# STM8L-FOX_80m_PA_V5_3.net
KiCad netlist of a schematic drawn in EAGLE
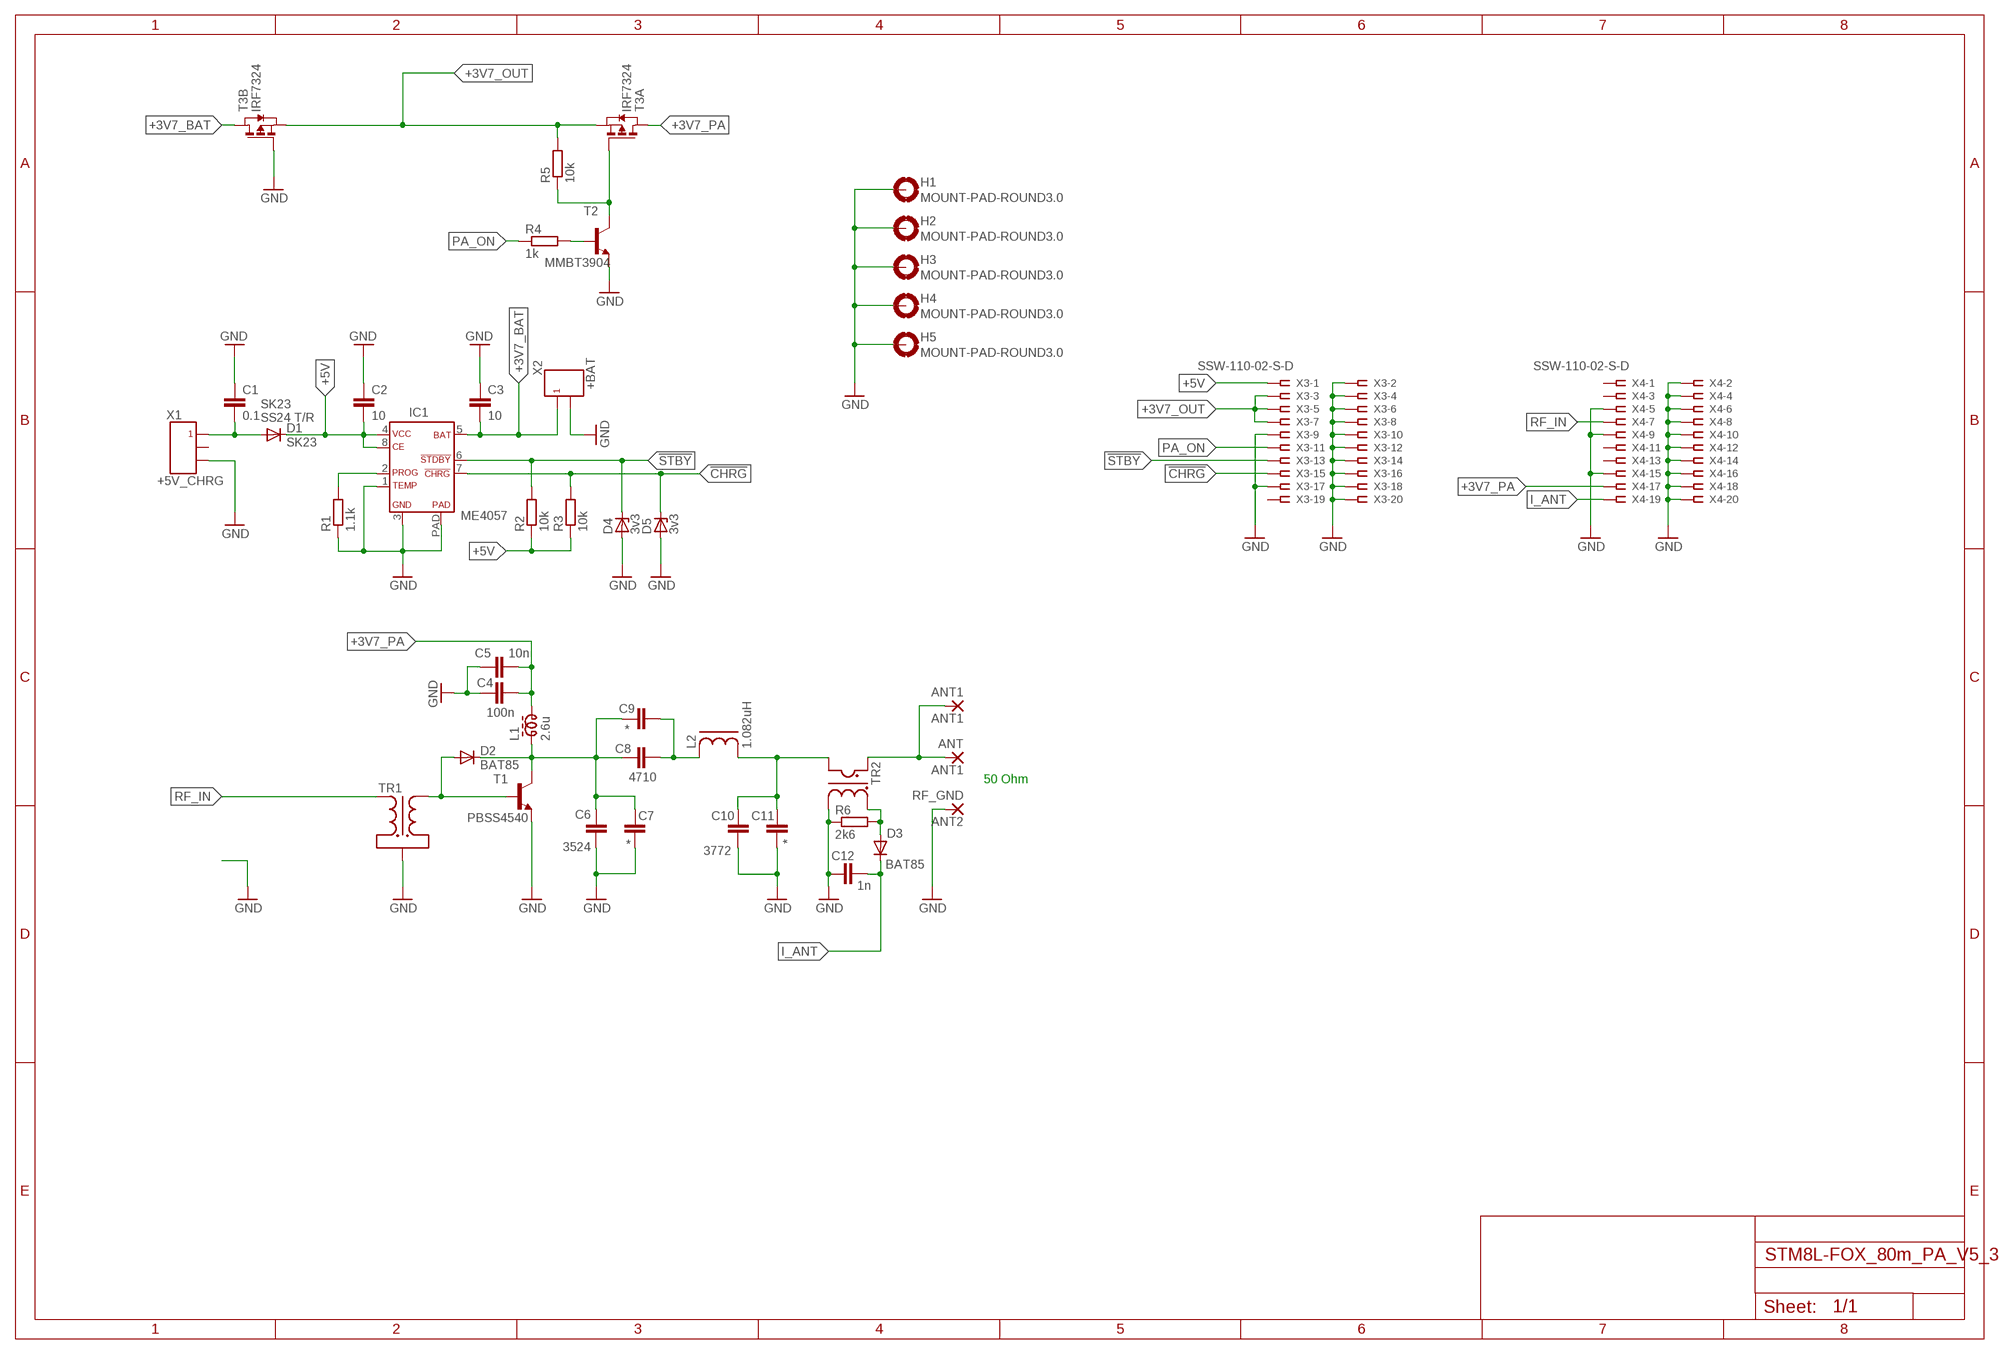
[diagram p0: schematic, sheet 1]

(export (version "E")
  (design (tool "Eeschema 10.0.6"))
  (components
    (comp (ref "ANT")
      (value "ANT1")
      (footprint "eagle-import:2,54_0,8")
      (libsource (lib "eagle-import") (part "WIREPAD2,54/0,8"))
    )
    (comp (ref "ANT1")
      (value "ANT1")
      (footprint "eagle-import:2,54_0,8")
      (libsource (lib "eagle-import") (part "WIREPAD2,54/0,8"))
    )
    (comp (ref "C1")
      (value "0.1")
      (footprint "eagle-import:C1206K")
      (libsource (lib "eagle-import") (part "C-EUC1206K"))
    )
    (comp (ref "C2")
      (value "10")
      (footprint "eagle-import:C1206K")
      (libsource (lib "eagle-import") (part "C-EUC1206K"))
    )
    (comp (ref "C3")
      (value "10")
      (footprint "eagle-import:C1206K")
      (libsource (lib "eagle-import") (part "C-EUC1206K"))
    )
    (comp (ref "C4")
      (value "100n")
      (footprint "eagle-import:C1206K")
      (libsource (lib "eagle-import") (part "C-EUC1206K"))
    )
    (comp (ref "C5")
      (value "10n")
      (footprint "eagle-import:C1206K")
      (libsource (lib "eagle-import") (part "C-EUC1206K"))
    )
    (comp (ref "C6")
      (value "3524")
      (footprint "eagle-import:C1206K")
      (libsource (lib "eagle-import") (part "C-EUC1206K"))
    )
    (comp (ref "C7")
      (value "*")
      (footprint "eagle-import:C1206K")
      (libsource (lib "eagle-import") (part "C-EUC1206K"))
    )
    (comp (ref "C8")
      (value "4710")
      (footprint "eagle-import:C1206K")
      (libsource (lib "eagle-import") (part "C-EUC1206K"))
    )
    (comp (ref "C9")
      (value "*")
      (footprint "eagle-import:C1206K")
      (libsource (lib "eagle-import") (part "C-EUC1206K"))
    )
    (comp (ref "C10")
      (value "3772")
      (footprint "eagle-import:C1206K")
      (libsource (lib "eagle-import") (part "C-EUC1206K"))
    )
    (comp (ref "C11")
      (value "*")
      (footprint "eagle-import:C1206K")
      (libsource (lib "eagle-import") (part "C-EUC1206K"))
    )
    (comp (ref "C12")
      (value "1n")
      (footprint "eagle-import:C1206K")
      (libsource (lib "eagle-import") (part "C-EUC1206K"))
    )
    (comp (ref "D1")
      (value "SK23")
      (footprint "eagle-import:DO-214AC")
      (libsource (lib "eagle-import") (part "DIODE-DO-214AC"))
    )
    (comp (ref "D2")
      (value "BAT85")
      (footprint "eagle-import:DO34-7")
      (libsource (lib "eagle-import") (part "BAT81"))
    )
    (comp (ref "D3")
      (value "BAT85")
      (footprint "eagle-import:DO34-7")
      (libsource (lib "eagle-import") (part "BAT81"))
    )
    (comp (ref "D4")
      (value "3v3")
      (footprint "eagle-import:SOT23")
      (libsource (lib "eagle-import") (part "ZENER-DIODESOT23"))
    )
    (comp (ref "D5")
      (value "3v3")
      (footprint "eagle-import:SOT23")
      (libsource (lib "eagle-import") (part "ZENER-DIODESOT23"))
    )
    (comp (ref "H1")
      (value "MOUNT-PAD-ROUND3.0")
      (footprint "eagle-import:3,0-PAD")
      (libsource (lib "eagle-import") (part "MOUNT-PAD-ROUND3.0"))
    )
    (comp (ref "H2")
      (value "MOUNT-PAD-ROUND3.0")
      (footprint "eagle-import:3,0-PAD")
      (libsource (lib "eagle-import") (part "MOUNT-PAD-ROUND3.0"))
    )
    (comp (ref "H3")
      (value "MOUNT-PAD-ROUND3.0")
      (footprint "eagle-import:3,0-PAD")
      (libsource (lib "eagle-import") (part "MOUNT-PAD-ROUND3.0"))
    )
    (comp (ref "H4")
      (value "MOUNT-PAD-ROUND3.0")
      (footprint "eagle-import:3,0-PAD")
      (libsource (lib "eagle-import") (part "MOUNT-PAD-ROUND3.0"))
    )
    (comp (ref "H5")
      (value "MOUNT-PAD-ROUND3.0")
      (footprint "eagle-import:3,0-PAD")
      (libsource (lib "eagle-import") (part "MOUNT-PAD-ROUND3.0"))
    )
    (comp (ref "IC1")
      (value "ME4057A")
      (footprint "eagle-import:SOP08-PP")
      (libsource (lib "eagle-import") (part "ME4057"))
    )
    (comp (ref "L1")
      (value "2.6u")
      (footprint "eagle-import:ZD6-3W")
      (libsource (lib "eagle-import") (part "ZD60820513"))
    )
    (comp (ref "L2")
      (value "1.082uH")
      (footprint "eagle-import:T68_COIL")
      (libsource (lib "eagle-import") (part "T68_COIL"))
    )
    (comp (ref "R1")
      (value "1.1k")
      (footprint "eagle-import:R1206")
      (libsource (lib "eagle-import") (part "R-EU_R1206"))
    )
    (comp (ref "R2")
      (value "10k")
      (footprint "eagle-import:R1206")
      (libsource (lib "eagle-import") (part "R-EU_R1206"))
    )
    (comp (ref "R3")
      (value "10k")
      (footprint "eagle-import:R1206")
      (libsource (lib "eagle-import") (part "R-EU_R1206"))
    )
    (comp (ref "R4")
      (value "1k")
      (footprint "eagle-import:R1206")
      (libsource (lib "eagle-import") (part "R-EU_R1206"))
    )
    (comp (ref "R5")
      (value "10k")
      (footprint "eagle-import:R1206")
      (libsource (lib "eagle-import") (part "R-EU_R1206"))
    )
    (comp (ref "R6")
      (value "2k6")
      (footprint "eagle-import:R1206")
      (libsource (lib "eagle-import") (part "R-EU_R1206"))
    )
    (comp (ref "RF_GND")
      (value "ANT2")
      (footprint "eagle-import:2,54_0,8")
      (libsource (lib "eagle-import") (part "WIREPAD2,54/0,8"))
    )
    (comp (ref "T1")
      (value "PBSS4540")
      (footprint "eagle-import:SOT223")
      (libsource (lib "eagle-import") (part "PBSS4540"))
    )
    (comp (ref "T2")
      (value "MMBT3904")
      (footprint "eagle-import:SOT23-BEC")
      (libsource (lib "eagle-import") (part "-NPN-SOT23-BECMMBT3904LT1"))
    )
    (comp (ref "T3")
      (value "IRF7324")
      (footprint "eagle-import:SO8")
      (libsource (lib "eagle-import") (part "PMOS2SO8"))
    )
    (comp (ref "TR1")
      (value "K7X4X2_TRANS_1V1")
      (footprint "eagle-import:K7X4X2_TRANS_1V1")
      (libsource (lib "eagle-import") (part "K7X4X2_TRANS_1V1"))
    )
    (comp (ref "TR2")
      (value "K7X4X2_TRANS_CURRENT")
      (footprint "eagle-import:K7X4X2_TRANS_CURRENT")
      (libsource (lib "eagle-import") (part "K7X4X2_TRANS_CURRENT"))
    )
    (comp (ref "X1")
      (value "+5V_CHRG")
      (footprint "eagle-import:A2501WR-3P")
      (libsource (lib "eagle-import") (part "A2501WR-3P"))
    )
    (comp (ref "X2")
      (value "+BAT")
      (footprint "eagle-import:A2501WR-2P")
      (libsource (lib "eagle-import") (part "A2501WR-2P"))
    )
    (comp (ref "X3")
      (value "SSW-110-02-S-D")
      (footprint "eagle-import:SSW-110-02-S-D")
      (libsource (lib "eagle-import") (part "SSW-110-02-S-D"))
    )
    (comp (ref "X4")
      (value "SSW-110-02-S-D")
      (footprint "eagle-import:SSW-110-02-S-D")
      (libsource (lib "eagle-import") (part "SSW-110-02-S-D"))
    )
  )
  (nets
    (net (code "1") (name "+3V7_BAT") (class "Default")
      (node (ref "C3") (pin "2") (pinfunction "2_2") (pintype "passive"))
      (node (ref "IC1") (pin "5") (pinfunction "P$5_5") (pintype "input"))
      (node (ref "T3") (pin "5") (pinfunction "D_5") (pintype "passive"))
      (node (ref "T3") (pin "6") (pinfunction "D_6") (pintype "passive"))
      (node (ref "X2") (pin "P$1") (pinfunction "P$1_P$1") (pintype "bidirectional"))
    )
    (net (code "2") (name "+3V7_OUT") (class "Default")
      (node (ref "R5") (pin "2") (pinfunction "2_2") (pintype "passive"))
      (node (ref "T3") (pin "1") (pinfunction "S_1") (pintype "passive"))
      (node (ref "T3") (pin "3") (pinfunction "S_3") (pintype "passive"))
      (node (ref "X3") (pin "3") (pinfunction "1_3") (pintype "passive"))
      (node (ref "X3") (pin "5") (pinfunction "1_5") (pintype "passive"))
      (node (ref "X3") (pin "7") (pinfunction "1_7") (pintype "passive"))
    )
    (net (code "3") (name "+3V7_PA") (class "Default")
      (node (ref "C4") (pin "2") (pinfunction "2_2") (pintype "passive"))
      (node (ref "C5") (pin "1") (pinfunction "1_1") (pintype "passive"))
      (node (ref "L1") (pin "2") (pinfunction "2_2") (pintype "passive"))
      (node (ref "T3") (pin "7") (pinfunction "D_7") (pintype "passive"))
      (node (ref "T3") (pin "8") (pinfunction "D_8") (pintype "passive"))
      (node (ref "X4") (pin "17") (pinfunction "1_17") (pintype "passive"))
    )
    (net (code "4") (name "+5V") (class "Default")
      (node (ref "C2") (pin "2") (pinfunction "2_2") (pintype "passive"))
      (node (ref "D1") (pin "C") (pinfunction "C_C") (pintype "passive"))
      (node (ref "IC1") (pin "4") (pinfunction "P$4_4") (pintype "input"))
      (node (ref "IC1") (pin "8") (pinfunction "P$8_8") (pintype "input"))
      (node (ref "R2") (pin "1") (pinfunction "1_1") (pintype "passive"))
      (node (ref "R3") (pin "1") (pinfunction "1_1") (pintype "passive"))
      (node (ref "X3") (pin "1") (pinfunction "1_1") (pintype "passive"))
    )
    (net (code "5") (name "/~{CHRG}") (class "Default")
      (node (ref "D5") (pin "3") (pinfunction "C_3") (pintype "passive"))
      (node (ref "IC1") (pin "7") (pinfunction "P$7_7") (pintype "output"))
      (node (ref "R3") (pin "2") (pinfunction "2_2") (pintype "passive"))
      (node (ref "X3") (pin "15") (pinfunction "1_15") (pintype "passive"))
    )
    (net (code "6") (name "/~{STBY}") (class "Default")
      (node (ref "D4") (pin "3") (pinfunction "C_3") (pintype "passive"))
      (node (ref "IC1") (pin "6") (pinfunction "P$6_6") (pintype "output"))
      (node (ref "R2") (pin "2") (pinfunction "2_2") (pintype "passive"))
      (node (ref "X3") (pin "13") (pinfunction "1_13") (pintype "passive"))
    )
    (net (code "7") (name "GND") (class "Default")
      (node (ref "C1") (pin "1") (pinfunction "1_1") (pintype "passive"))
      (node (ref "C10") (pin "2") (pinfunction "2_2") (pintype "passive"))
      (node (ref "C11") (pin "2") (pinfunction "2_2") (pintype "passive"))
      (node (ref "C12") (pin "1") (pinfunction "1_1") (pintype "passive"))
      (node (ref "C2") (pin "1") (pinfunction "1_1") (pintype "passive"))
      (node (ref "C3") (pin "1") (pinfunction "1_1") (pintype "passive"))
      (node (ref "C4") (pin "1") (pinfunction "1_1") (pintype "passive"))
      (node (ref "C5") (pin "2") (pinfunction "2_2") (pintype "passive"))
      (node (ref "C6") (pin "2") (pinfunction "2_2") (pintype "passive"))
      (node (ref "C7") (pin "2") (pinfunction "2_2") (pintype "passive"))
      (node (ref "D4") (pin "1") (pinfunction "A_1") (pintype "passive"))
      (node (ref "D5") (pin "1") (pinfunction "A_1") (pintype "passive"))
      (node (ref "H1") (pin "B3,0") (pinfunction "MOUNT_B3,0") (pintype "passive"))
      (node (ref "H2") (pin "B3,0") (pinfunction "MOUNT_B3,0") (pintype "passive"))
      (node (ref "H3") (pin "B3,0") (pinfunction "MOUNT_B3,0") (pintype "passive"))
      (node (ref "H4") (pin "B3,0") (pinfunction "MOUNT_B3,0") (pintype "passive"))
      (node (ref "H5") (pin "B3,0") (pinfunction "MOUNT_B3,0") (pintype "passive"))
      (node (ref "IC1") (pin "1") (pinfunction "P$1_1") (pintype "input"))
      (node (ref "IC1") (pin "3") (pinfunction "P$3_3") (pintype "input"))
      (node (ref "IC1") (pin "PAD") (pinfunction "P$9_PAD") (pintype "passive"))
      (node (ref "R1") (pin "1") (pinfunction "1_1") (pintype "passive"))
      (node (ref "R6") (pin "1") (pinfunction "1_1") (pintype "passive"))
      (node (ref "RF_GND") (pin "1") (pinfunction "P_1") (pintype "passive"))
      (node (ref "T1") (pin "3") (pinfunction "E_3") (pintype "passive"))
      (node (ref "T2") (pin "E") (pinfunction "E_E") (pintype "passive"))
      (node (ref "T3") (pin "4") (pinfunction "G_4") (pintype "passive"))
      (node (ref "TR1") (pin "P$1") (pinfunction "P$1_P$1") (pintype "input"))
      (node (ref "TR2") (pin "P$4") (pinfunction "P$4_P$4") (pintype "input"))
      (node (ref "X1") (pin "P$3") (pinfunction "P$3_P$3") (pintype "bidirectional"))
      (node (ref "X2") (pin "P$2") (pinfunction "P$2_P$2") (pintype "bidirectional"))
      (node (ref "X3") (pin "10") (pinfunction "1_10") (pintype "passive"))
      (node (ref "X3") (pin "12") (pinfunction "1_12") (pintype "passive"))
      (node (ref "X3") (pin "14") (pinfunction "1_14") (pintype "passive"))
      (node (ref "X3") (pin "16") (pinfunction "1_16") (pintype "passive"))
      (node (ref "X3") (pin "17") (pinfunction "1_17") (pintype "passive"))
      (node (ref "X3") (pin "18") (pinfunction "1_18") (pintype "passive"))
      (node (ref "X3") (pin "2") (pinfunction "1_2") (pintype "passive"))
      (node (ref "X3") (pin "20") (pinfunction "1_20") (pintype "passive"))
      (node (ref "X3") (pin "4") (pinfunction "1_4") (pintype "passive"))
      (node (ref "X3") (pin "6") (pinfunction "1_6") (pintype "passive"))
      (node (ref "X3") (pin "8") (pinfunction "1_8") (pintype "passive"))
      (node (ref "X3") (pin "9") (pinfunction "1_9") (pintype "passive"))
      (node (ref "X4") (pin "10") (pinfunction "1_10") (pintype "passive"))
      (node (ref "X4") (pin "12") (pinfunction "1_12") (pintype "passive"))
      (node (ref "X4") (pin "14") (pinfunction "1_14") (pintype "passive"))
      (node (ref "X4") (pin "15") (pinfunction "1_15") (pintype "passive"))
      (node (ref "X4") (pin "16") (pinfunction "1_16") (pintype "passive"))
      (node (ref "X4") (pin "18") (pinfunction "1_18") (pintype "passive"))
      (node (ref "X4") (pin "2") (pinfunction "1_2") (pintype "passive"))
      (node (ref "X4") (pin "20") (pinfunction "1_20") (pintype "passive"))
      (node (ref "X4") (pin "4") (pinfunction "1_4") (pintype "passive"))
      (node (ref "X4") (pin "5") (pinfunction "1_5") (pintype "passive"))
      (node (ref "X4") (pin "6") (pinfunction "1_6") (pintype "passive"))
      (node (ref "X4") (pin "8") (pinfunction "1_8") (pintype "passive"))
      (node (ref "X4") (pin "9") (pinfunction "1_9") (pintype "passive"))
    )
    (net (code "8") (name "I_ANT") (class "Default")
      (node (ref "C12") (pin "2") (pinfunction "2_2") (pintype "passive"))
      (node (ref "D3") (pin "C") (pinfunction "C_C") (pintype "passive"))
      (node (ref "X4") (pin "19") (pinfunction "1_19") (pintype "passive"))
    )
    (net (code "9") (name "Net-(ANT-P)") (class "Default")
      (node (ref "ANT") (pin "1") (pinfunction "P_1") (pintype "passive"))
      (node (ref "ANT1") (pin "1") (pinfunction "P_1") (pintype "passive"))
      (node (ref "TR2") (pin "P$1") (pinfunction "P$1_P$1") (pintype "input"))
    )
    (net (code "10") (name "Net-(C1-Pad2)") (class "Default")
      (node (ref "C1") (pin "2") (pinfunction "2_2") (pintype "passive"))
      (node (ref "D1") (pin "A") (pinfunction "A_A") (pintype "passive"))
      (node (ref "X1") (pin "P$1") (pinfunction "P$1_P$1") (pintype "bidirectional"))
    )
    (net (code "11") (name "Net-(C6-Pad1)") (class "Default")
      (node (ref "C6") (pin "1") (pinfunction "1_1") (pintype "passive"))
      (node (ref "C7") (pin "1") (pinfunction "1_1") (pintype "passive"))
      (node (ref "C8") (pin "1") (pinfunction "1_1") (pintype "passive"))
      (node (ref "C9") (pin "1") (pinfunction "1_1") (pintype "passive"))
      (node (ref "D2") (pin "C") (pinfunction "C_C") (pintype "passive"))
      (node (ref "L1") (pin "1") (pinfunction "1_1") (pintype "passive"))
      (node (ref "T1") (pin "2") (pinfunction "C_2") (pintype "passive"))
      (node (ref "T1") (pin "4") (pinfunction "C_4") (pintype "passive"))
    )
    (net (code "12") (name "Net-(C8-Pad2)") (class "Default")
      (node (ref "C8") (pin "2") (pinfunction "2_2") (pintype "passive"))
      (node (ref "C9") (pin "2") (pinfunction "2_2") (pintype "passive"))
      (node (ref "L2") (pin "P$1") (pinfunction "P$1_P$1") (pintype "input"))
    )
    (net (code "13") (name "Net-(C10-Pad1)") (class "Default")
      (node (ref "C10") (pin "1") (pinfunction "1_1") (pintype "passive"))
      (node (ref "C11") (pin "1") (pinfunction "1_1") (pintype "passive"))
      (node (ref "L2") (pin "P$2") (pinfunction "P$2_P$2") (pintype "input"))
      (node (ref "TR2") (pin "P$2") (pinfunction "P$2_P$2") (pintype "input"))
    )
    (net (code "14") (name "Net-(D3-PadA)") (class "Default")
      (node (ref "D3") (pin "A") (pinfunction "A_A") (pintype "passive"))
      (node (ref "R6") (pin "2") (pinfunction "2_2") (pintype "passive"))
      (node (ref "TR2") (pin "P$3") (pinfunction "P$3_P$3") (pintype "input"))
    )
    (net (code "15") (name "Net-(IC1-P$2)") (class "Default")
      (node (ref "IC1") (pin "2") (pinfunction "P$2_2") (pintype "input"))
      (node (ref "R1") (pin "2") (pinfunction "2_2") (pintype "passive"))
    )
    (net (code "16") (name "Net-(R4-Pad2)") (class "Default")
      (node (ref "R4") (pin "2") (pinfunction "2_2") (pintype "passive"))
      (node (ref "T2") (pin "B") (pinfunction "B_B") (pintype "passive"))
    )
    (net (code "17") (name "Net-(T1-B)") (class "Default")
      (node (ref "D2") (pin "A") (pinfunction "A_A") (pintype "passive"))
      (node (ref "T1") (pin "1") (pinfunction "B_1") (pintype "passive"))
      (node (ref "TR1") (pin "P$3") (pinfunction "P$3_P$3") (pintype "input"))
    )
    (net (code "18") (name "Net-(T3A-G)") (class "Default")
      (node (ref "R5") (pin "1") (pinfunction "1_1") (pintype "passive"))
      (node (ref "T2") (pin "C") (pinfunction "C_C") (pintype "passive"))
      (node (ref "T3") (pin "2") (pinfunction "G_2") (pintype "passive"))
    )
    (net (code "19") (name "PA_ON") (class "Default")
      (node (ref "R4") (pin "1") (pinfunction "1_1") (pintype "passive"))
      (node (ref "X3") (pin "11") (pinfunction "1_11") (pintype "passive"))
    )
    (net (code "20") (name "RF_IN") (class "Default")
      (node (ref "TR1") (pin "P$2") (pinfunction "P$2_P$2") (pintype "input"))
      (node (ref "X4") (pin "7") (pinfunction "1_7") (pintype "passive"))
    )
    (net (code "21") (name "unconnected-(L2-PadP$3)") (class "Default")
      (node (ref "L2") (pin "P$3") (pinfunction "P$3_P$3") (pintype "no_connect"))
    )
    (net (code "22") (name "unconnected-(L2-PadP$4)") (class "Default")
      (node (ref "L2") (pin "P$4") (pinfunction "P$4_P$4") (pintype "no_connect"))
    )
    (net (code "23") (name "unconnected-(TR1-PadP$4)") (class "Default")
      (node (ref "TR1") (pin "P$4") (pinfunction "P$4_P$4") (pintype "no_connect"))
    )
    (net (code "24") (name "unconnected-(TR1-PadP$5)") (class "Default")
      (node (ref "TR1") (pin "P$5") (pinfunction "P$5_P$5") (pintype "no_connect"))
    )
    (net (code "25") (name "unconnected-(X1-PadP$2)") (class "Default")
      (node (ref "X1") (pin "P$2") (pinfunction "P$2_P$2") (pintype "bidirectional"))
    )
    (net (code "26") (name "unconnected-(X3K-1-Pad19)") (class "Default")
      (node (ref "X3") (pin "19") (pinfunction "1_19") (pintype "passive"))
    )
    (net (code "27") (name "unconnected-(X4-Pad1)") (class "Default")
      (node (ref "X4") (pin "1") (pinfunction "1_1") (pintype "passive"))
    )
    (net (code "28") (name "unconnected-(X4C-1-Pad11)") (class "Default")
      (node (ref "X4") (pin "11") (pinfunction "1_11") (pintype "passive"))
    )
    (net (code "29") (name "unconnected-(X4E-1-Pad13)") (class "Default")
      (node (ref "X4") (pin "13") (pinfunction "1_13") (pintype "passive"))
    )
    (net (code "30") (name "unconnected-(X4N-1-Pad3)") (class "Default")
      (node (ref "X4") (pin "3") (pinfunction "1_3") (pintype "passive"))
    )
  )
)
